# RFM232_V01.net
KiCad netlist of a schematic drawn in Altium Designer
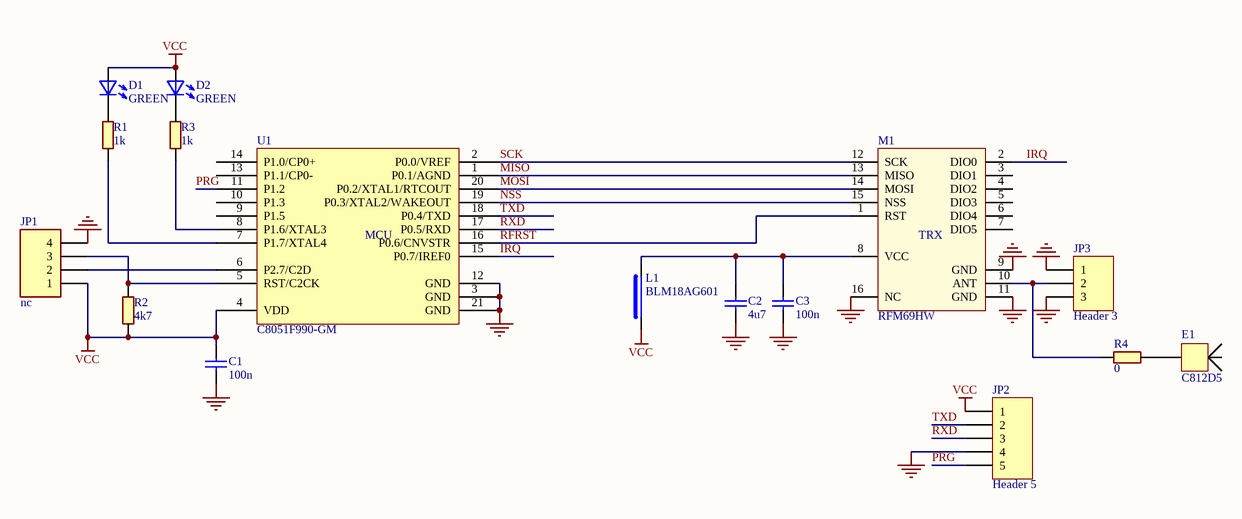
[diagram p0: RFM232_V01.SchDoc]

(export (version "E")
  (design (tool "Eeschema 10.0.6"))
  (components
    (comp (ref "C1") (value "100n") (footprint "CAPC1608X08N") (libsource (lib "Discrete") (part "CAPN")))
    (comp (ref "C2") (value "4u7") (footprint "CAPC2012X11N") (libsource (lib "Discrete") (part "CAPN")))
    (comp (ref "C3") (value "100n") (footprint "CAPC1608X08N") (libsource (lib "Discrete") (part "CAPN")))
    (comp (ref "D1")
      (value "GREEN")
      (footprint "LEDC200X125X80L40N")
      (libsource (lib "Discrete") (part "DLED"))
    )
    (comp (ref "D2")
      (value "GREEN")
      (footprint "LEDC200X125X80L40N")
      (libsource (lib "Discrete") (part "DLED"))
    )
    (comp (ref "E1") (value "C812D5") (footprint "C812D5") (libsource (lib "RFUART") (part "C812D5")))
    (comp (ref "JP1")
      (value "nc")
      (footprint "HDRV4W70P254_4X1_889X254H754")
      (description "4 Pin Header 2,0 mm, 1x04")
      (libsource (lib "e4") (part "HEADER 4"))
    )
    (comp (ref "JP2")
      (value "Header 5")
      (footprint "HDRV5W70P254_5X1_1143X254H754")
      (description "Header, 5-Pin")
      (fields (field (name "PUBLISHER") "Altium Limited"))
      (libsource (lib "Miscellaneous Connectors") (part "Header 5"))
    )
    (comp (ref "JP3")
      (value "Header 3")
      (footprint "HDRV3W70P254_3X1_635X254H754")
      (description "Header, 3-Pin")
      (fields (field (name "PUBLISHER") "Altium Limited"))
      (libsource (lib "Miscellaneous Connectors") (part "Header 3"))
    )
    (comp (ref "L1")
      (value "BLM18AG601")
      (footprint "INDC1608X10N")
      (libsource (lib "Discrete") (part "SUPRESOR"))
    )
    (comp (ref "M1")
      (value "RFM69HW")
      (footprint "LGA16_RFM69")
      (libsource (lib "CLAP_M505_WL_BP_V22") (part "RFM69HW_V13_2"))
    )
    (comp (ref "R1") (value "1k") (footprint "RESC1608X06N") (libsource (lib "") (part "RES_1")))
    (comp (ref "R2") (value "4k7") (footprint "RESC1608X06N") (libsource (lib "Discrete") (part "RES")))
    (comp (ref "R3") (value "1k") (footprint "RESC1608X06N") (libsource (lib "") (part "RES_1")))
    (comp (ref "R4") (value "0") (footprint "RESC2012X07N") (libsource (lib "") (part "RES_2")))
    (comp (ref "U1")
      (value "C8051F990-GM")
      (footprint "QFN50P300X300X60_HS-21N")
      (libsource (lib "ES1004") (part "C8051F990"))
    )
  )
  (nets
    (net (code "1") (name "/IRQ") (class "Default")
      (node (ref "M1") (pin "2") (pinfunction "DIO0_2") (pintype "passive"))
      (node (ref "U1") (pin "15") (pinfunction "P0.7/IREF0_15") (pintype "passive"))
    )
    (net (code "2") (name "/MISO") (class "Default")
      (node (ref "M1") (pin "13") (pinfunction "MISO_13") (pintype "passive"))
      (node (ref "U1") (pin "1") (pinfunction "P0.1/AGND_1") (pintype "passive"))
    )
    (net (code "3") (name "/MOSI") (class "Default")
      (node (ref "M1") (pin "14") (pinfunction "MOSI_14") (pintype "passive"))
      (node (ref "U1") (pin "20") (pinfunction "P0.2/XTAL1/RTCOUT_20") (pintype "passive"))
    )
    (net (code "4") (name "/NSS") (class "Default")
      (node (ref "M1") (pin "15") (pinfunction "NSS_15") (pintype "passive"))
      (node (ref "U1") (pin "19") (pinfunction "P0.3/XTAL2/WAKEOUT_19") (pintype "passive"))
    )
    (net (code "5") (name "/PRG") (class "Default")
      (node (ref "JP2") (pin "5") (pinfunction "5_5") (pintype "passive"))
      (node (ref "U1") (pin "11") (pinfunction "P1.2_11") (pintype "passive"))
    )
    (net (code "6") (name "/RFRST") (class "Default")
      (node (ref "M1") (pin "1") (pinfunction "RST_1") (pintype "passive"))
      (node (ref "U1") (pin "16") (pinfunction "P0.6/CNVSTR_16") (pintype "passive"))
    )
    (net (code "7") (name "/RXD") (class "Default")
      (node (ref "JP2") (pin "3") (pinfunction "3_3") (pintype "passive"))
      (node (ref "U1") (pin "17") (pinfunction "P0.5/RXD_17") (pintype "passive"))
    )
    (net (code "8") (name "/SCK") (class "Default")
      (node (ref "M1") (pin "12") (pinfunction "SCK_12") (pintype "passive"))
      (node (ref "U1") (pin "2") (pinfunction "P0.0/VREF_2") (pintype "passive"))
    )
    (net (code "9") (name "/TXD") (class "Default")
      (node (ref "JP2") (pin "2") (pinfunction "2_2") (pintype "passive"))
      (node (ref "U1") (pin "18") (pinfunction "P0.4/TXD_18") (pintype "passive"))
    )
    (net (code "10") (name "GND") (class "Default")
      (node (ref "C1") (pin "2") (pinfunction "2_2") (pintype "passive"))
      (node (ref "C2") (pin "2") (pinfunction "2_2") (pintype "passive"))
      (node (ref "C3") (pin "2") (pinfunction "2_2") (pintype "passive"))
      (node (ref "JP1") (pin "4") (pinfunction "4_4") (pintype "passive"))
      (node (ref "JP2") (pin "4") (pinfunction "4_4") (pintype "passive"))
      (node (ref "JP3") (pin "1") (pinfunction "1_1") (pintype "passive"))
      (node (ref "JP3") (pin "3") (pinfunction "3_3") (pintype "passive"))
      (node (ref "M1") (pin "11") (pinfunction "GND_11") (pintype "passive"))
      (node (ref "M1") (pin "16") (pinfunction "NC_16") (pintype "passive"))
      (node (ref "M1") (pin "9") (pinfunction "GND_9") (pintype "passive"))
      (node (ref "U1") (pin "12") (pinfunction "GND_12") (pintype "passive"))
      (node (ref "U1") (pin "21") (pinfunction "GND_21") (pintype "passive"))
      (node (ref "U1") (pin "3") (pinfunction "GND_3") (pintype "passive"))
    )
    (net (code "11") (name "Net-(D1-2)") (class "Default")
      (node (ref "D1") (pin "K") (pinfunction "2_K") (pintype "passive"))
      (node (ref "R1") (pin "1") (pinfunction "1_1") (pintype "passive"))
    )
    (net (code "12") (name "Net-(D2-2)") (class "Default")
      (node (ref "D2") (pin "K") (pinfunction "2_K") (pintype "passive"))
      (node (ref "R3") (pin "1") (pinfunction "1_1") (pintype "passive"))
    )
    (net (code "13") (name "Net-(E1-IN)") (class "Default")
      (node (ref "E1") (pin "1") (pinfunction "IN_1") (pintype "passive"))
      (node (ref "R4") (pin "2") (pinfunction "2_2") (pintype "passive"))
    )
    (net (code "14") (name "Net-(M1-ANT)") (class "Default")
      (node (ref "JP3") (pin "2") (pinfunction "2_2") (pintype "passive"))
      (node (ref "M1") (pin "10") (pinfunction "ANT_10") (pintype "passive"))
      (node (ref "R4") (pin "1") (pinfunction "1_1") (pintype "passive"))
    )
    (net (code "15") (name "Net-(M1-VCC)") (class "Default")
      (node (ref "C2") (pin "1") (pinfunction "1_1") (pintype "passive"))
      (node (ref "C3") (pin "1") (pinfunction "1_1") (pintype "passive"))
      (node (ref "L1") (pin "2") (pinfunction "2_2") (pintype "passive"))
      (node (ref "M1") (pin "8") (pinfunction "VCC_8") (pintype "passive"))
    )
    (net (code "16") (name "Net-(U1-P1.6{slash}XTAL3)") (class "Default")
      (node (ref "R3") (pin "2") (pinfunction "2_2") (pintype "passive"))
      (node (ref "U1") (pin "8") (pinfunction "P1.6/XTAL3_8") (pintype "passive"))
    )
    (net (code "17") (name "Net-(U1-P1.7{slash}XTAL4)") (class "Default")
      (node (ref "R1") (pin "2") (pinfunction "2_2") (pintype "passive"))
      (node (ref "U1") (pin "7") (pinfunction "P1.7/XTAL4_7") (pintype "passive"))
    )
    (net (code "18") (name "Net-(U1-P2.7{slash}C2D)") (class "Default")
      (node (ref "JP1") (pin "2") (pinfunction "2_2") (pintype "passive"))
      (node (ref "U1") (pin "6") (pinfunction "P2.7/C2D_6") (pintype "passive"))
    )
    (net (code "19") (name "Net-(U1-RST{slash}C2CK)") (class "Default")
      (node (ref "JP1") (pin "3") (pinfunction "3_3") (pintype "passive"))
      (node (ref "R2") (pin "1") (pinfunction "1_1") (pintype "passive"))
      (node (ref "U1") (pin "5") (pinfunction "RST/C2CK_5") (pintype "passive"))
    )
    (net (code "20") (name "VCC") (class "Default")
      (node (ref "C1") (pin "1") (pinfunction "1_1") (pintype "passive"))
      (node (ref "D1") (pin "A") (pinfunction "1_A") (pintype "passive"))
      (node (ref "D2") (pin "A") (pinfunction "1_A") (pintype "passive"))
      (node (ref "JP1") (pin "1") (pinfunction "1_1") (pintype "passive"))
      (node (ref "JP2") (pin "1") (pinfunction "1_1") (pintype "passive"))
      (node (ref "L1") (pin "1") (pinfunction "1_1") (pintype "passive"))
      (node (ref "R2") (pin "2") (pinfunction "2_2") (pintype "passive"))
      (node (ref "U1") (pin "4") (pinfunction "VDD_4") (pintype "passive"))
    )
    (net (code "21") (name "unconnected-(M1-DIO1-Pad3)") (class "Default")
      (node (ref "M1") (pin "3") (pinfunction "DIO1_3") (pintype "passive"))
    )
    (net (code "22") (name "unconnected-(M1-DIO2-Pad4)") (class "Default")
      (node (ref "M1") (pin "4") (pinfunction "DIO2_4") (pintype "passive"))
    )
    (net (code "23") (name "unconnected-(M1-DIO3-Pad5)") (class "Default")
      (node (ref "M1") (pin "5") (pinfunction "DIO3_5") (pintype "passive"))
    )
    (net (code "24") (name "unconnected-(M1-DIO4-Pad6)") (class "Default")
      (node (ref "M1") (pin "6") (pinfunction "DIO4_6") (pintype "passive"))
    )
    (net (code "25") (name "unconnected-(M1-DIO5-Pad7)") (class "Default")
      (node (ref "M1") (pin "7") (pinfunction "DIO5_7") (pintype "passive"))
    )
    (net (code "26") (name "unconnected-(U1-P1.0{slash}CP0+-Pad14)") (class "Default")
      (node (ref "U1") (pin "14") (pinfunction "P1.0/CP0+_14") (pintype "passive"))
    )
    (net (code "27") (name "unconnected-(U1-P1.1{slash}CP0--Pad13)") (class "Default")
      (node (ref "U1") (pin "13") (pinfunction "P1.1/CP0-_13") (pintype "passive"))
    )
    (net (code "28") (name "unconnected-(U1-P1.3-Pad10)") (class "Default")
      (node (ref "U1") (pin "10") (pinfunction "P1.3_10") (pintype "passive"))
    )
    (net (code "29") (name "unconnected-(U1-P1.5-Pad9)") (class "Default")
      (node (ref "U1") (pin "9") (pinfunction "P1.5_9") (pintype "passive"))
    )
  )
)
